# Inverter_540VDC_V2_TEST.net
KiCad netlist of a schematic drawn in Altium Designer
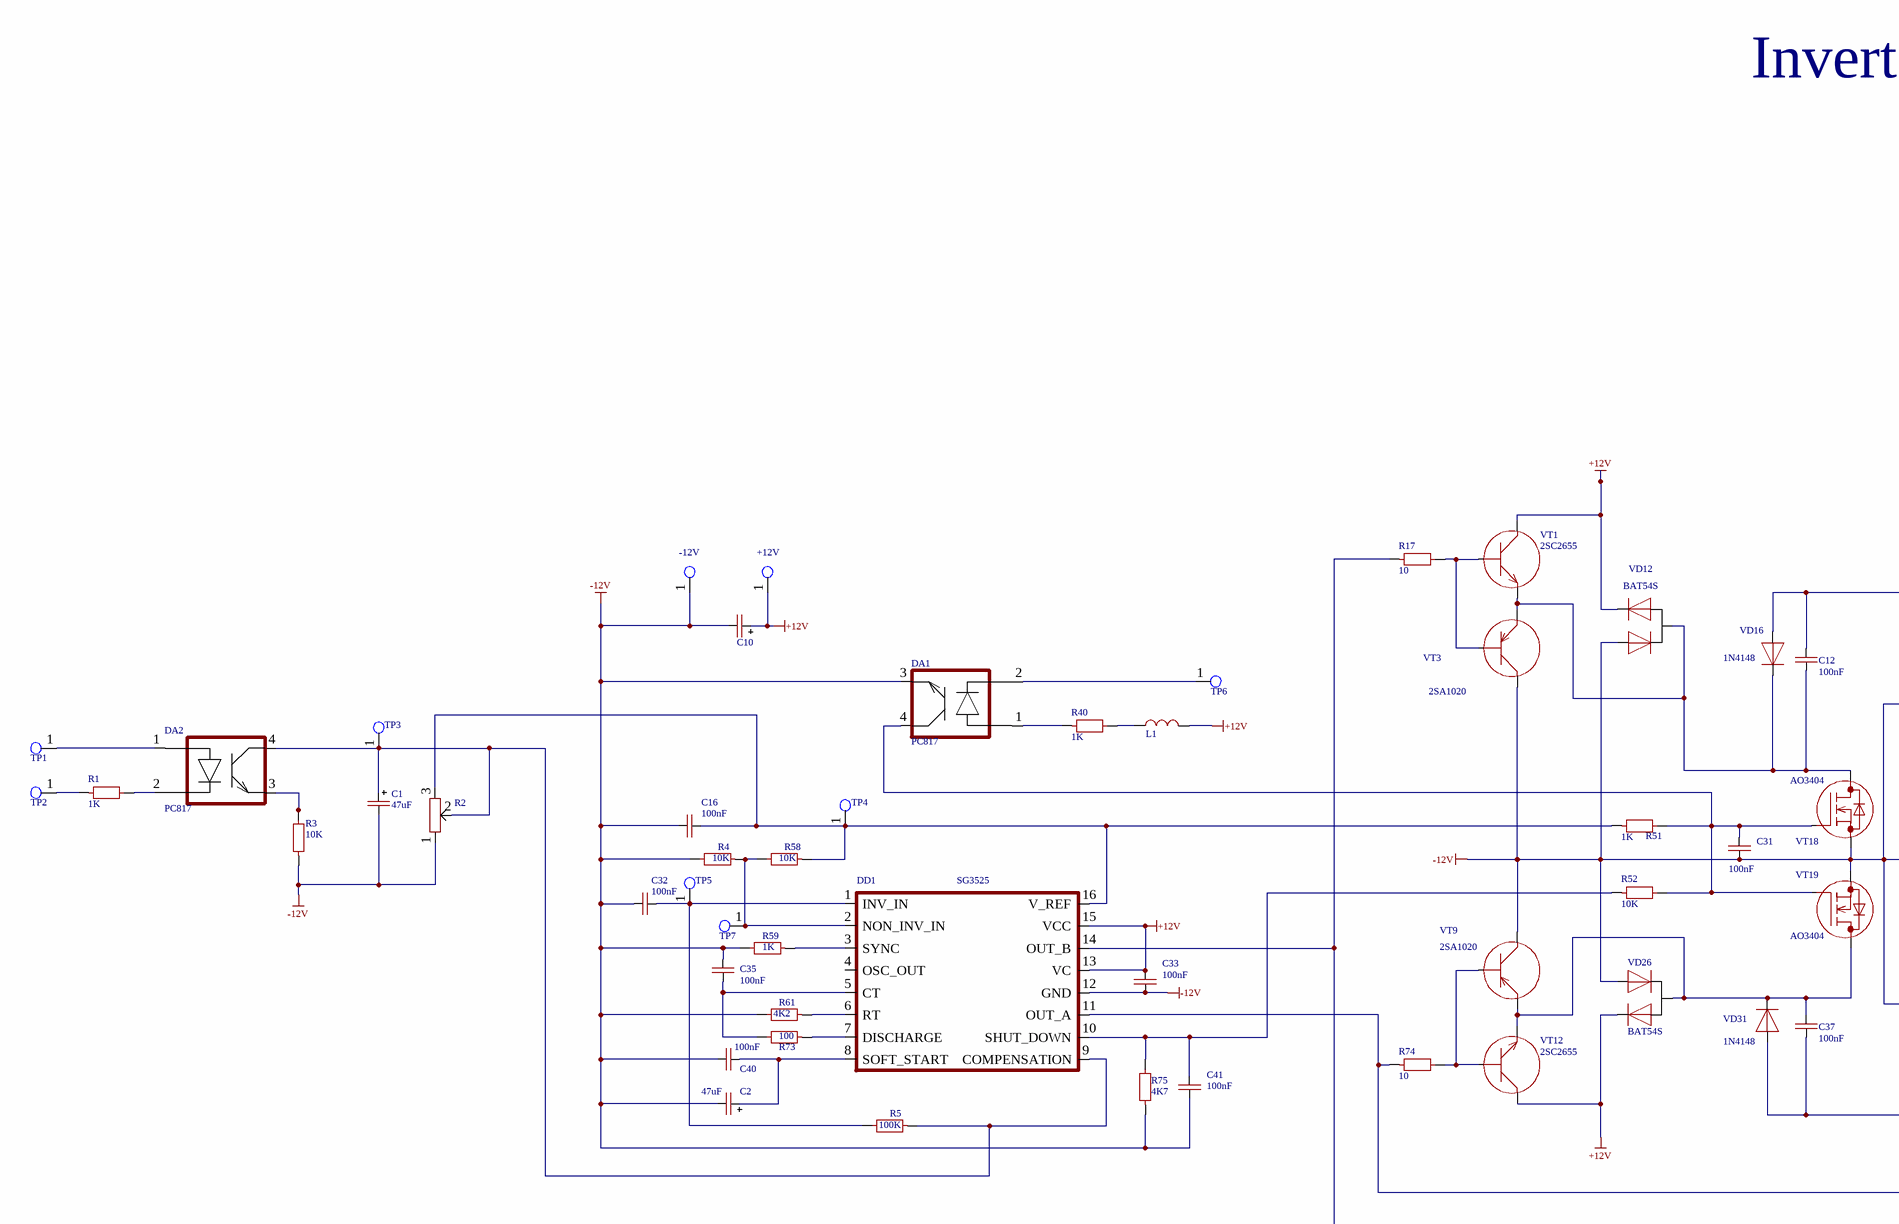
[diagram p0: Inverter_540VDC_V2_TEST.SchDoc, left]
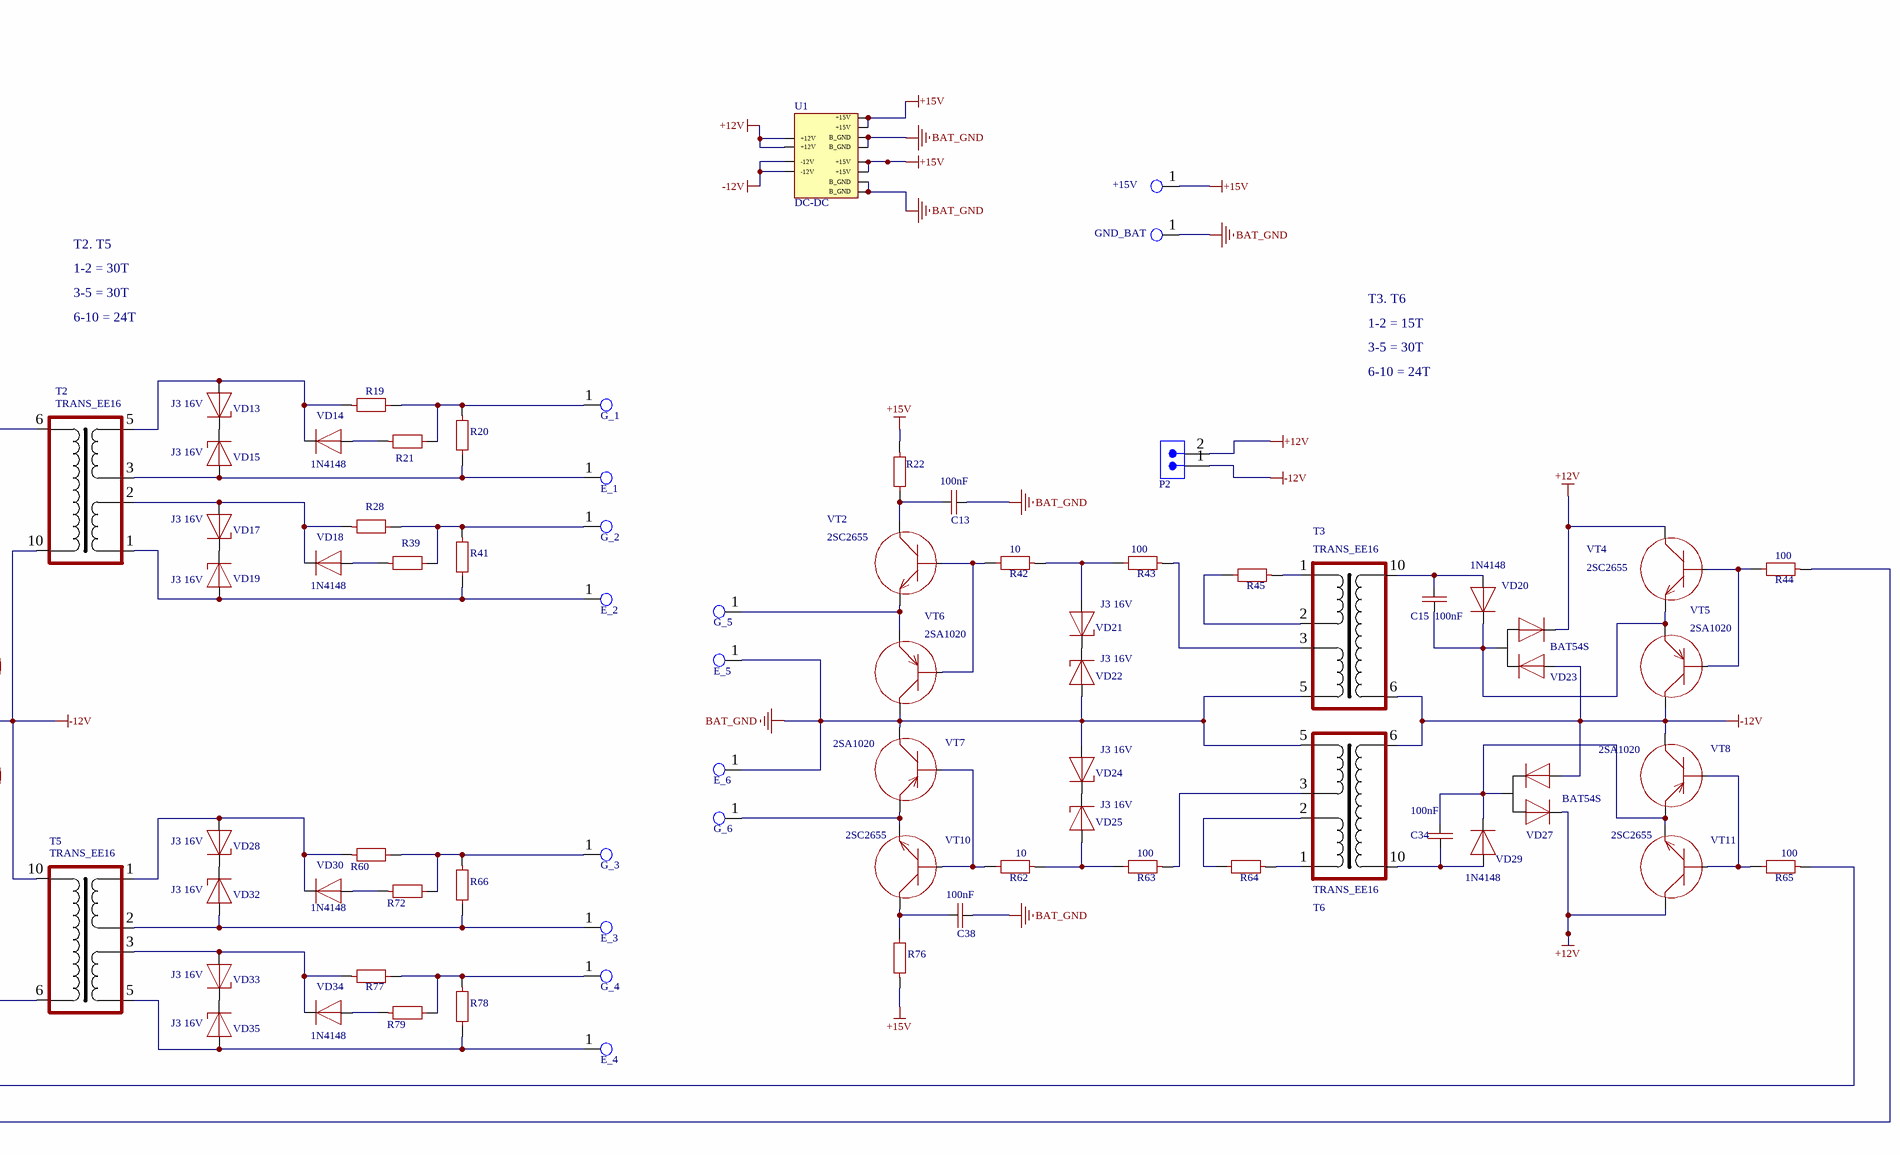
[diagram p1: Inverter_540VDC_V2_TEST.SchDoc, right]

(export (version "E")
  (design (tool "Eeschema 10.0.6"))
  (components
    (comp (ref "+12V")
      (value "Test_Point_PCB")
      (footprint "Test_Point")
      (description "Test_Point")
      (libsource (lib "TEST_POINT") (part "TP_PCB?"))
    )
    (comp (ref "+15V")
      (value "Test_Point_PCB")
      (footprint "Test_Point")
      (description "Test_Point")
      (libsource (lib "TEST_POINT") (part "TP_PCB?"))
    )
    (comp (ref "-12V")
      (value "Test_Point_PCB")
      (footprint "Test_Point")
      (description "Test_Point")
      (libsource (lib "TEST_POINT") (part "TP_PCB?"))
    )
    (comp (ref "C1")
      (value "47uF")
      (footprint "CAP-TAN-C")
      (libsource (lib "PAS_COMPONENTS") (part "CAP-POLAR"))
    )
    (comp (ref "C2")
      (value "47uF")
      (footprint "CAP-TAN-C")
      (libsource (lib "PAS_COMPONENTS") (part "CAP-POLAR"))
    )
    (comp (ref "C10")
      (value "CAP-POLAR")
      (footprint "CAPPOL_SMD_SIZE_E")
      (libsource (lib "PAS_COMPONENTS") (part "CAP-POLAR"))
    )
    (comp (ref "C12")
      (value "100nF")
      (footprint "CAP-1206")
      (libsource (lib "PAS_COMPONENTS") (part "CAP-NON-POLAR"))
    )
    (comp (ref "C13")
      (value "100nF")
      (footprint "CAP-0805")
      (libsource (lib "PAS_COMPONENTS") (part "CAP-NON-POLAR"))
    )
    (comp (ref "C15")
      (value "100nF")
      (footprint "CAP-1206")
      (libsource (lib "PAS_COMPONENTS") (part "CAP-NON-POLAR"))
    )
    (comp (ref "C16")
      (value "100nF")
      (footprint "CAP-0805")
      (libsource (lib "PAS_COMPONENTS") (part "CAP-NON-POLAR"))
    )
    (comp (ref "C31")
      (value "100nF")
      (footprint "CAP-1206")
      (libsource (lib "PAS_COMPONENTS") (part "CAP-NON-POLAR"))
    )
    (comp (ref "C32")
      (value "100nF")
      (footprint "CAP-0805")
      (libsource (lib "PAS_COMPONENTS") (part "CAP-NON-POLAR"))
    )
    (comp (ref "C33")
      (value "100nF")
      (footprint "CAP-0805")
      (libsource (lib "PAS_COMPONENTS") (part "CAP-NON-POLAR"))
    )
    (comp (ref "C34")
      (value "100nF")
      (footprint "CAP-1206")
      (libsource (lib "PAS_COMPONENTS") (part "CAP-NON-POLAR"))
    )
    (comp (ref "C35")
      (value "100nF")
      (footprint "CAP-0805")
      (libsource (lib "PAS_COMPONENTS") (part "CAP-NON-POLAR"))
    )
    (comp (ref "C37")
      (value "100nF")
      (footprint "CAP-1206")
      (libsource (lib "PAS_COMPONENTS") (part "CAP-NON-POLAR"))
    )
    (comp (ref "C38")
      (value "100nF")
      (footprint "CAP-0805")
      (libsource (lib "PAS_COMPONENTS") (part "CAP-NON-POLAR"))
    )
    (comp (ref "C40")
      (value "100nF")
      (footprint "CAP-0805")
      (libsource (lib "PAS_COMPONENTS") (part "CAP-NON-POLAR"))
    )
    (comp (ref "C41")
      (value "100nF")
      (footprint "CAP-0805")
      (libsource (lib "PAS_COMPONENTS") (part "CAP-NON-POLAR"))
    )
    (comp (ref "DA1") (value "PC817") (footprint "4-SMD") (libsource (lib "PC817") (part "PC817")))
    (comp (ref "DA2") (value "PC817") (footprint "4-SMD") (libsource (lib "") (part "PC817_1")))
    (comp (ref "DD1") (value "SG3525") (footprint "SO16-150") (libsource (lib "SG3525") (part "SG3525")))
    (comp (ref "E_1")
      (value "Test_Point_PCB")
      (footprint "Test_Point")
      (description "Test_Point")
      (libsource (lib "TEST_POINT") (part "TP_PCB?"))
    )
    (comp (ref "E_2")
      (value "Test_Point_PCB")
      (footprint "Test_Point")
      (description "Test_Point")
      (libsource (lib "TEST_POINT") (part "TP_PCB?"))
    )
    (comp (ref "E_3")
      (value "Test_Point_PCB")
      (footprint "Test_Point")
      (description "Test_Point")
      (libsource (lib "TEST_POINT") (part "TP_PCB?"))
    )
    (comp (ref "E_4")
      (value "Test_Point_PCB")
      (footprint "Test_Point")
      (description "Test_Point")
      (libsource (lib "TEST_POINT") (part "TP_PCB?"))
    )
    (comp (ref "E_5")
      (value "Test_Point_PCB")
      (footprint "Test_Point")
      (description "Test_Point")
      (libsource (lib "TEST_POINT") (part "TP_PCB?"))
    )
    (comp (ref "E_6")
      (value "Test_Point_PCB")
      (footprint "Test_Point")
      (description "Test_Point")
      (libsource (lib "TEST_POINT") (part "TP_PCB?"))
    )
    (comp (ref "GND_BAT")
      (value "Test_Point_PCB")
      (footprint "Test_Point")
      (description "Test_Point")
      (libsource (lib "TEST_POINT") (part "TP_PCB?"))
    )
    (comp (ref "G_1")
      (value "Test_Point_PCB")
      (footprint "Test_Point")
      (description "Test_Point")
      (libsource (lib "TEST_POINT") (part "TP_PCB?"))
    )
    (comp (ref "G_2")
      (value "Test_Point_PCB")
      (footprint "Test_Point")
      (description "Test_Point")
      (libsource (lib "TEST_POINT") (part "TP_PCB?"))
    )
    (comp (ref "G_3")
      (value "Test_Point_PCB")
      (footprint "Test_Point")
      (description "Test_Point")
      (libsource (lib "TEST_POINT") (part "TP_PCB?"))
    )
    (comp (ref "G_4")
      (value "Test_Point_PCB")
      (footprint "Test_Point")
      (description "Test_Point")
      (libsource (lib "TEST_POINT") (part "TP_PCB?"))
    )
    (comp (ref "G_5")
      (value "Test_Point_PCB")
      (footprint "Test_Point")
      (description "Test_Point")
      (libsource (lib "TEST_POINT") (part "TP_PCB?"))
    )
    (comp (ref "G_6")
      (value "Test_Point_PCB")
      (footprint "Test_Point")
      (description "Test_Point")
      (libsource (lib "TEST_POINT") (part "TP_PCB?"))
    )
    (comp (ref "L1")
      (value "IND-CONST")
      (footprint "IND-7850")
      (libsource (lib "PAS_COMPONENTS") (part "IND-CONST"))
    )
    (comp (ref "P2")
      (value "691701530002B")
      (footprint "691701530002B")
      (description "WR-TBL Series 7015B Open Horizontal PCB Header, SMT, pitch 5.08mm, 2p")
      (fields (field (name "MANUFACTURER") "Wurth Elektronik"))
      (libsource (lib "Altium_WR-TBL (rev23f)") (part "691701530002B"))
    )
    (comp (ref "R1")
      (value "1K")
      (footprint "RES-0805")
      (description "10K")
      (libsource (lib "PAS_COMPONENTS") (part "RES-CONST"))
    )
    (comp (ref "R2") (value "3296W") (footprint "3296W") (libsource (lib "3296W") (part "3296W")))
    (comp (ref "R3")
      (value "10K")
      (footprint "RES-0805")
      (libsource (lib "PAS_COMPONENTS") (part "RES-CONST"))
    )
    (comp (ref "R4")
      (value "10K")
      (footprint "RES-0805")
      (libsource (lib "PAS_COMPONENTS") (part "RES-CONST"))
    )
    (comp (ref "R5")
      (value "100K")
      (footprint "RES-0805")
      (description "10K")
      (libsource (lib "PAS_COMPONENTS") (part "RES-CONST"))
    )
    (comp (ref "R17")
      (value "10")
      (footprint "RES-1206")
      (libsource (lib "PAS_COMPONENTS") (part "RES-CONST"))
    )
    (comp (ref "R19")
      (value "RES-CONST")
      (footprint "RES-1206")
      (libsource (lib "PAS_COMPONENTS") (part "RES-CONST"))
    )
    (comp (ref "R20")
      (value "RES-CONST")
      (footprint "RES-1206")
      (libsource (lib "PAS_COMPONENTS") (part "RES-CONST"))
    )
    (comp (ref "R21")
      (value "RES-CONST")
      (footprint "RES-1206")
      (libsource (lib "PAS_COMPONENTS") (part "RES-CONST"))
    )
    (comp (ref "R22")
      (value "RES-CONST")
      (footprint "RES-2512")
      (libsource (lib "PAS_COMPONENTS") (part "RES-CONST"))
    )
    (comp (ref "R28")
      (value "RES-CONST")
      (footprint "RES-1206")
      (libsource (lib "PAS_COMPONENTS") (part "RES-CONST"))
    )
    (comp (ref "R39")
      (value "RES-CONST")
      (footprint "RES-1206")
      (libsource (lib "PAS_COMPONENTS") (part "RES-CONST"))
    )
    (comp (ref "R40")
      (value "1K")
      (footprint "RES-0805")
      (libsource (lib "PAS_COMPONENTS") (part "RES-CONST"))
    )
    (comp (ref "R41")
      (value "RES-CONST")
      (footprint "RES-1206")
      (libsource (lib "PAS_COMPONENTS") (part "RES-CONST"))
    )
    (comp (ref "R42")
      (value "10")
      (footprint "RES-1206")
      (libsource (lib "PAS_COMPONENTS") (part "RES-CONST"))
    )
    (comp (ref "R43")
      (value "100")
      (footprint "RES-1206")
      (libsource (lib "PAS_COMPONENTS") (part "RES-CONST"))
    )
    (comp (ref "R44")
      (value "100")
      (footprint "RES-1206")
      (libsource (lib "PAS_COMPONENTS") (part "RES-CONST"))
    )
    (comp (ref "R45")
      (value "RES-CONST")
      (footprint "RES-2512")
      (libsource (lib "PAS_COMPONENTS") (part "RES-CONST"))
    )
    (comp (ref "R51")
      (value "1K")
      (footprint "RES-1206")
      (libsource (lib "PAS_COMPONENTS") (part "RES-CONST"))
    )
    (comp (ref "R52")
      (value "10K")
      (footprint "RES-1206")
      (libsource (lib "PAS_COMPONENTS") (part "RES-CONST"))
    )
    (comp (ref "R58")
      (value "10K")
      (footprint "RES-0805")
      (libsource (lib "PAS_COMPONENTS") (part "RES-CONST"))
    )
    (comp (ref "R59")
      (value "1K")
      (footprint "RES-0805")
      (libsource (lib "PAS_COMPONENTS") (part "RES-CONST"))
    )
    (comp (ref "R60")
      (value "RES-CONST")
      (footprint "RES-1206")
      (libsource (lib "PAS_COMPONENTS") (part "RES-CONST"))
    )
    (comp (ref "R61")
      (value "4K2")
      (footprint "RES-0805")
      (libsource (lib "PAS_COMPONENTS") (part "RES-CONST"))
    )
    (comp (ref "R62")
      (value "10")
      (footprint "RES-1206")
      (libsource (lib "PAS_COMPONENTS") (part "RES-CONST"))
    )
    (comp (ref "R63")
      (value "100")
      (footprint "RES-1206")
      (libsource (lib "PAS_COMPONENTS") (part "RES-CONST"))
    )
    (comp (ref "R64")
      (value "RES-CONST")
      (footprint "RES-2512")
      (libsource (lib "PAS_COMPONENTS") (part "RES-CONST"))
    )
    (comp (ref "R65")
      (value "100")
      (footprint "RES-1206")
      (libsource (lib "PAS_COMPONENTS") (part "RES-CONST"))
    )
    (comp (ref "R66")
      (value "RES-CONST")
      (footprint "RES-1206")
      (libsource (lib "PAS_COMPONENTS") (part "RES-CONST"))
    )
    (comp (ref "R72")
      (value "RES-CONST")
      (footprint "RES-1206")
      (libsource (lib "PAS_COMPONENTS") (part "RES-CONST"))
    )
    (comp (ref "R73")
      (value "100")
      (footprint "RES-0805")
      (libsource (lib "PAS_COMPONENTS") (part "RES-CONST"))
    )
    (comp (ref "R74")
      (value "10")
      (footprint "RES-1206")
      (libsource (lib "PAS_COMPONENTS") (part "RES-CONST"))
    )
    (comp (ref "R75")
      (value "4K7")
      (footprint "RES-0805")
      (libsource (lib "PAS_COMPONENTS") (part "RES-CONST"))
    )
    (comp (ref "R76")
      (value "RES-CONST")
      (footprint "RES-2512")
      (libsource (lib "PAS_COMPONENTS") (part "RES-CONST"))
    )
    (comp (ref "R77")
      (value "RES-CONST")
      (footprint "RES-1206")
      (libsource (lib "PAS_COMPONENTS") (part "RES-CONST"))
    )
    (comp (ref "R78")
      (value "RES-CONST")
      (footprint "RES-1206")
      (libsource (lib "PAS_COMPONENTS") (part "RES-CONST"))
    )
    (comp (ref "R79")
      (value "RES-CONST")
      (footprint "RES-1206")
      (libsource (lib "PAS_COMPONENTS") (part "RES-CONST"))
    )
    (comp (ref "T2")
      (value "TRANS_EE16")
      (footprint "TRANS_EE16")
      (libsource (lib "TRANS_EE16") (part "TRANS_EE16"))
    )
    (comp (ref "T3")
      (value "TRANS_EE16")
      (footprint "TRANS_EE16")
      (libsource (lib "TRANS_EE16") (part "TRANS_EE16"))
    )
    (comp (ref "T5") (value "TRANS_EE16") (footprint "TRANS_EE16") (libsource (lib "") (part "TRANS_EE16_1")))
    (comp (ref "T6") (value "TRANS_EE16") (footprint "TRANS_EE16") (libsource (lib "") (part "TRANS_EE16_1")))
    (comp (ref "TP1")
      (value "Test_Point_PCB")
      (footprint "Test_Point")
      (description "Test_Point")
      (libsource (lib "TEST_POINT") (part "TP_PCB?"))
    )
    (comp (ref "TP2")
      (value "Test_Point_PCB")
      (footprint "Test_Point")
      (description "Test_Point")
      (libsource (lib "TEST_POINT") (part "TP_PCB?"))
    )
    (comp (ref "TP3")
      (value "Test_Point_PCB")
      (footprint "Test_Point")
      (description "Test_Point")
      (libsource (lib "TEST_POINT") (part "TP_PCB?"))
    )
    (comp (ref "TP4")
      (value "Test_Point_PCB")
      (footprint "Test_Point")
      (description "Test_Point")
      (libsource (lib "TEST_POINT") (part "TP_PCB?"))
    )
    (comp (ref "TP5")
      (value "Test_Point_PCB")
      (footprint "Test_Point")
      (description "Test_Point")
      (libsource (lib "TEST_POINT") (part "TP_PCB?"))
    )
    (comp (ref "TP6")
      (value "Test_Point_PCB")
      (footprint "Test_Point")
      (description "Test_Point")
      (libsource (lib "TEST_POINT") (part "TP_PCB?"))
    )
    (comp (ref "TP7")
      (value "Test_Point_PCB")
      (footprint "Test_Point")
      (description "Test_Point")
      (libsource (lib "TEST_POINT") (part "TP_PCB?"))
    )
    (comp (ref "U1")
      (value "DC-DC")
      (footprint "DC-DC_Bridge")
      (libsource (lib "PWM_Controllers") (part "DC-DC/12-18VDC"))
    )
    (comp (ref "VD12") (value "BAT54S") (footprint "SOT23-3") (libsource (lib "DIODES") (part "DIODE-4")))
    (comp (ref "VD13") (value "J3 16V") (footprint "SOD-123") (libsource (lib "DIODES") (part "ZENER")))
    (comp (ref "VD14") (value "1N4148") (footprint "SOD-123") (libsource (lib "DIODES") (part "DIODE")))
    (comp (ref "VD15") (value "J3 16V") (footprint "SOD-123") (libsource (lib "DIODES") (part "ZENER")))
    (comp (ref "VD16") (value "1N4148") (footprint "SOD-123") (libsource (lib "DIODES") (part "DIODE")))
    (comp (ref "VD17") (value "J3 16V") (footprint "SOD-123") (libsource (lib "DIODES") (part "ZENER")))
    (comp (ref "VD18") (value "1N4148") (footprint "SOD-123") (libsource (lib "DIODES") (part "DIODE")))
    (comp (ref "VD19") (value "J3 16V") (footprint "SOD-123") (libsource (lib "DIODES") (part "ZENER")))
    (comp (ref "VD20") (value "1N4148") (footprint "SOD-123") (libsource (lib "DIODES") (part "DIODE")))
    (comp (ref "VD21") (value "J3 16V") (footprint "SOD-123") (libsource (lib "DIODES") (part "ZENER")))
    (comp (ref "VD22") (value "J3 16V") (footprint "SOD-123") (libsource (lib "DIODES") (part "ZENER")))
    (comp (ref "VD23") (value "BAT54S") (footprint "SOT23-3") (libsource (lib "DIODES") (part "DIODE-4")))
    (comp (ref "VD24") (value "J3 16V") (footprint "SOD-123") (libsource (lib "DIODES") (part "ZENER")))
    (comp (ref "VD25") (value "J3 16V") (footprint "SOD-123") (libsource (lib "DIODES") (part "ZENER")))
    (comp (ref "VD26") (value "BAT54S") (footprint "SOT23-3") (libsource (lib "DIODES") (part "DIODE-4")))
    (comp (ref "VD27") (value "BAT54S") (footprint "SOT23-3") (libsource (lib "DIODES") (part "DIODE-4")))
    (comp (ref "VD28") (value "J3 16V") (footprint "SOD-123") (libsource (lib "DIODES") (part "ZENER")))
    (comp (ref "VD29") (value "1N4148") (footprint "SOD-123") (libsource (lib "DIODES") (part "DIODE")))
    (comp (ref "VD30") (value "1N4148") (footprint "SOD-123") (libsource (lib "DIODES") (part "DIODE")))
    (comp (ref "VD31") (value "1N4148") (footprint "SOD-123") (libsource (lib "DIODES") (part "DIODE")))
    (comp (ref "VD32") (value "J3 16V") (footprint "SOD-123") (libsource (lib "DIODES") (part "ZENER")))
    (comp (ref "VD33") (value "J3 16V") (footprint "SOD-123") (libsource (lib "DIODES") (part "ZENER")))
    (comp (ref "VD34") (value "1N4148") (footprint "SOD-123") (libsource (lib "DIODES") (part "DIODE")))
    (comp (ref "VD35") (value "J3 16V") (footprint "SOD-123") (libsource (lib "DIODES") (part "ZENER")))
    (comp (ref "VT1")
      (value "2SC2655")
      (footprint "SOT-89")
      (libsource (lib "TRANSISTORS") (part "BIPOLAR-NPN-BEC"))
    )
    (comp (ref "VT2")
      (value "2SC2655")
      (footprint "SOT-89")
      (libsource (lib "TRANSISTORS") (part "BIPOLAR-NPN-BEC"))
    )
    (comp (ref "VT3")
      (value "2SA1020")
      (footprint "SOT-89")
      (libsource (lib "TRANSISTORS") (part "BIPOLAR-PNP-BCE"))
    )
    (comp (ref "VT4")
      (value "2SC2655")
      (footprint "SOT-89")
      (libsource (lib "TRANSISTORS") (part "BIPOLAR-NPN-BEC"))
    )
    (comp (ref "VT5")
      (value "2SA1020")
      (footprint "SOT-89")
      (libsource (lib "TRANSISTORS") (part "BIPOLAR-PNP-BCE"))
    )
    (comp (ref "VT6")
      (value "2SA1020")
      (footprint "SOT-89")
      (libsource (lib "TRANSISTORS") (part "BIPOLAR-PNP-BCE"))
    )
    (comp (ref "VT7")
      (value "2SA1020")
      (footprint "SOT-89")
      (libsource (lib "TRANSISTORS") (part "BIPOLAR-PNP-BCE"))
    )
    (comp (ref "VT8")
      (value "2SA1020")
      (footprint "SOT-89")
      (libsource (lib "TRANSISTORS") (part "BIPOLAR-PNP-BCE"))
    )
    (comp (ref "VT9")
      (value "2SA1020")
      (footprint "SOT-89")
      (libsource (lib "TRANSISTORS") (part "BIPOLAR-PNP-BCE"))
    )
    (comp (ref "VT10")
      (value "2SC2655")
      (footprint "SOT-89")
      (libsource (lib "TRANSISTORS") (part "BIPOLAR-NPN-BEC"))
    )
    (comp (ref "VT11")
      (value "2SC2655")
      (footprint "SOT-89")
      (libsource (lib "TRANSISTORS") (part "BIPOLAR-NPN-BEC"))
    )
    (comp (ref "VT12")
      (value "2SC2655")
      (footprint "SOT-89")
      (libsource (lib "TRANSISTORS") (part "BIPOLAR-NPN-BEC"))
    )
    (comp (ref "VT18")
      (value "AO3404")
      (footprint "SOT23-3")
      (libsource (lib "TRANSISTORS") (part "MOSFET-N-GDS"))
    )
    (comp (ref "VT19")
      (value "AO3404")
      (footprint "SOT23-3")
      (libsource (lib "TRANSISTORS") (part "MOSFET-N-GDS"))
    )
  )
  (nets
    (net (code "1") (name "+12V") (class "Default")
      (node (ref "+12V") (pin "1") (pinfunction "G9_1") (pintype "passive"))
      (node (ref "C10") (pin "1") (pinfunction "+_1") (pintype "passive"))
      (node (ref "C33") (pin "2") (pinfunction "2_2") (pintype "passive"))
      (node (ref "DD1") (pin "13") (pinfunction "VC_13") (pintype "passive"))
      (node (ref "DD1") (pin "15") (pinfunction "VCC_15") (pintype "passive"))
      (node (ref "L1") (pin "2") (pinfunction "2_2") (pintype "passive"))
      (node (ref "P2") (pin "2") (pinfunction "2_2") (pintype "passive"))
      (node (ref "U1") (pin "8") (pinfunction "+12V_8") (pintype "passive"))
      (node (ref "U1") (pin "9") (pinfunction "+12V_9") (pintype "passive"))
      (node (ref "VD12") (pin "2") (pinfunction "C_2") (pintype "passive"))
      (node (ref "VD23") (pin "2") (pinfunction "C_2") (pintype "passive"))
      (node (ref "VD26") (pin "2") (pinfunction "C_2") (pintype "passive"))
      (node (ref "VD27") (pin "2") (pinfunction "C_2") (pintype "passive"))
      (node (ref "VT1") (pin "2") (pinfunction "C_2") (pintype "passive"))
      (node (ref "VT11") (pin "2") (pinfunction "C_2") (pintype "passive"))
      (node (ref "VT12") (pin "2") (pinfunction "C_2") (pintype "passive"))
      (node (ref "VT4") (pin "2") (pinfunction "C_2") (pintype "passive"))
    )
    (net (code "2") (name "+15V") (class "Default")
      (node (ref "+15V") (pin "1") (pinfunction "G9_1") (pintype "passive"))
      (node (ref "R22") (pin "1") (pinfunction "1_1") (pintype "passive"))
      (node (ref "R76") (pin "1") (pinfunction "1_1") (pintype "passive"))
      (node (ref "U1") (pin "1") (pinfunction "+15V_1") (pintype "passive"))
      (node (ref "U1") (pin "17") (pinfunction "+15V_17") (pintype "passive"))
      (node (ref "U1") (pin "18") (pinfunction "+15V_18") (pintype "passive"))
      (node (ref "U1") (pin "2") (pinfunction "+15V_2") (pintype "passive"))
    )
    (net (code "3") (name "-12V") (class "Default")
      (node (ref "-12V") (pin "1") (pinfunction "G9_1") (pintype "passive"))
      (node (ref "C1") (pin "2") (pinfunction "-_2") (pintype "passive"))
      (node (ref "C10") (pin "2") (pinfunction "-_2") (pintype "passive"))
      (node (ref "C16") (pin "2") (pinfunction "2_2") (pintype "passive"))
      (node (ref "C2") (pin "2") (pinfunction "-_2") (pintype "passive"))
      (node (ref "C31") (pin "1") (pinfunction "1_1") (pintype "passive"))
      (node (ref "C32") (pin "2") (pinfunction "2_2") (pintype "passive"))
      (node (ref "C33") (pin "1") (pinfunction "1_1") (pintype "passive"))
      (node (ref "C35") (pin "1") (pinfunction "1_1") (pintype "passive"))
      (node (ref "C40") (pin "2") (pinfunction "2_2") (pintype "passive"))
      (node (ref "C41") (pin "1") (pinfunction "1_1") (pintype "passive"))
      (node (ref "DA1") (pin "3") (pinfunction "EMITTER_3") (pintype "passive"))
      (node (ref "DD1") (pin "12") (pinfunction "GND_12") (pintype "passive"))
      (node (ref "P2") (pin "1") (pinfunction "1_1") (pintype "passive"))
      (node (ref "R2") (pin "1") (pinfunction "1_1") (pintype "passive"))
      (node (ref "R3") (pin "1") (pinfunction "1_1") (pintype "passive"))
      (node (ref "R4") (pin "2") (pinfunction "2_2") (pintype "passive"))
      (node (ref "R59") (pin "2") (pinfunction "2_2") (pintype "passive"))
      (node (ref "R61") (pin "2") (pinfunction "2_2") (pintype "passive"))
      (node (ref "R75") (pin "1") (pinfunction "1_1") (pintype "passive"))
      (node (ref "T2") (pin "10") (pintype "passive"))
      (node (ref "T3") (pin "6") (pintype "passive"))
      (node (ref "T5") (pin "10") (pintype "passive"))
      (node (ref "T6") (pin "6") (pintype "passive"))
      (node (ref "U1") (pin "10") (pinfunction "-12V_10") (pintype "passive"))
      (node (ref "U1") (pin "11") (pinfunction "-12V_11") (pintype "passive"))
      (node (ref "VD12") (pin "1") (pinfunction "A_1") (pintype "passive"))
      (node (ref "VD23") (pin "1") (pinfunction "A_1") (pintype "passive"))
      (node (ref "VD26") (pin "1") (pinfunction "A_1") (pintype "passive"))
      (node (ref "VD27") (pin "1") (pinfunction "A_1") (pintype "passive"))
      (node (ref "VT18") (pin "2") (pinfunction "S_2") (pintype "passive"))
      (node (ref "VT19") (pin "2") (pinfunction "S_2") (pintype "passive"))
      (node (ref "VT3") (pin "2") (pinfunction "C_2") (pintype "passive"))
      (node (ref "VT5") (pin "2") (pinfunction "C_2") (pintype "passive"))
      (node (ref "VT8") (pin "2") (pinfunction "C_2") (pintype "passive"))
      (node (ref "VT9") (pin "2") (pinfunction "C_2") (pintype "passive"))
    )
    (net (code "4") (name "BAT_GND") (class "Default")
      (node (ref "C13") (pin "1") (pinfunction "1_1") (pintype "passive"))
      (node (ref "C38") (pin "1") (pinfunction "1_1") (pintype "passive"))
      (node (ref "E_5") (pin "1") (pinfunction "G9_1") (pintype "passive"))
      (node (ref "E_6") (pin "1") (pinfunction "G9_1") (pintype "passive"))
      (node (ref "GND_BAT") (pin "1") (pinfunction "G9_1") (pintype "passive"))
      (node (ref "T3") (pin "5") (pintype "passive"))
      (node (ref "T6") (pin "5") (pintype "passive"))
      (node (ref "U1") (pin "15") (pinfunction "B_GND_15") (pintype "passive"))
      (node (ref "U1") (pin "16") (pinfunction "B_GND_16") (pintype "passive"))
      (node (ref "U1") (pin "3") (pinfunction "B_GND_3") (pintype "passive"))
      (node (ref "U1") (pin "4") (pinfunction "B_GND_4") (pintype "passive"))
      (node (ref "VD22") (pin "2") (pinfunction "A_2") (pintype "passive"))
      (node (ref "VD24") (pin "2") (pinfunction "A_2") (pintype "passive"))
      (node (ref "VT6") (pin "2") (pinfunction "C_2") (pintype "passive"))
      (node (ref "VT7") (pin "2") (pinfunction "C_2") (pintype "passive"))
    )
    (net (code "5") (name "Net-(C1-+)") (class "Default")
      (node (ref "C1") (pin "1") (pinfunction "+_1") (pintype "passive"))
      (node (ref "DA2") (pin "4") (pinfunction "COLLECTOR_4") (pintype "passive"))
      (node (ref "DD1") (pin "9") (pinfunction "COMPENSATION_9") (pintype "passive"))
      (node (ref "R2") (pin "2") (pinfunction "2_2") (pintype "passive"))
      (node (ref "R5") (pin "1") (pinfunction "1_1") (pintype "passive"))
      (node (ref "TP3") (pin "1") (pinfunction "G9_1") (pintype "passive"))
    )
    (net (code "6") (name "Net-(C2-+)") (class "Default")
      (node (ref "C2") (pin "1") (pinfunction "+_1") (pintype "passive"))
      (node (ref "C40") (pin "1") (pinfunction "1_1") (pintype "passive"))
      (node (ref "DD1") (pin "8") (pinfunction "SOFT_START_8") (pintype "passive"))
    )
    (net (code "7") (name "Net-(DA1-ANODE)") (class "Default")
      (node (ref "DA1") (pin "1") (pinfunction "ANODE_1") (pintype "passive"))
      (node (ref "R40") (pin "1") (pinfunction "1_1") (pintype "passive"))
    )
    (net (code "8") (name "Net-(DA1-CATHODE)") (class "Default")
      (node (ref "DA1") (pin "2") (pinfunction "CATHODE_2") (pintype "passive"))
      (node (ref "TP6") (pin "1") (pinfunction "G9_1") (pintype "passive"))
    )
    (net (code "9") (name "Net-(DA1-COLLECTOR)") (class "Default")
      (node (ref "C31") (pin "2") (pinfunction "2_2") (pintype "passive"))
      (node (ref "DA1") (pin "4") (pinfunction "COLLECTOR_4") (pintype "passive"))
      (node (ref "R51") (pin "2") (pinfunction "2_2") (pintype "passive"))
      (node (ref "R52") (pin "2") (pinfunction "2_2") (pintype "passive"))
      (node (ref "VT18") (pin "1") (pinfunction "G_1") (pintype "passive"))
      (node (ref "VT19") (pin "1") (pinfunction "G_1") (pintype "passive"))
    )
    (net (code "10") (name "Net-(DA2-ANODE)") (class "Default")
      (node (ref "DA2") (pin "1") (pinfunction "ANODE_1") (pintype "passive"))
      (node (ref "TP1") (pin "1") (pinfunction "G9_1") (pintype "passive"))
    )
    (net (code "11") (name "Net-(DA2-CATHODE)") (class "Default")
      (node (ref "DA2") (pin "2") (pinfunction "CATHODE_2") (pintype "passive"))
      (node (ref "R1") (pin "2") (pinfunction "2_2") (pintype "passive"))
    )
    (net (code "12") (name "Net-(DA2-EMITTER)") (class "Default")
      (node (ref "DA2") (pin "3") (pinfunction "EMITTER_3") (pintype "passive"))
      (node (ref "R3") (pin "2") (pinfunction "2_2") (pintype "passive"))
    )
    (net (code "13") (name "Net-(DD1-CT)") (class "Default")
      (node (ref "C35") (pin "2") (pinfunction "2_2") (pintype "passive"))
      (node (ref "DD1") (pin "5") (pinfunction "CT_5") (pintype "passive"))
      (node (ref "R73") (pin "2") (pinfunction "2_2") (pintype "passive"))
    )
    (net (code "14") (name "Net-(DD1-DISCHARGE)") (class "Default")
      (node (ref "DD1") (pin "7") (pinfunction "DISCHARGE_7") (pintype "passive"))
      (node (ref "R73") (pin "1") (pinfunction "1_1") (pintype "passive"))
    )
    (net (code "15") (name "Net-(DD1-INV_IN)") (class "Default")
      (node (ref "C32") (pin "1") (pinfunction "1_1") (pintype "passive"))
      (node (ref "DD1") (pin "1") (pinfunction "INV_IN_1") (pintype "passive"))
      (node (ref "R5") (pin "2") (pinfunction "2_2") (pintype "passive"))
      (node (ref "TP5") (pin "1") (pinfunction "G9_1") (pintype "passive"))
    )
    (net (code "16") (name "Net-(DD1-NON_INV_IN)") (class "Default")
      (node (ref "DD1") (pin "2") (pinfunction "NON_INV_IN_2") (pintype "passive"))
      (node (ref "R4") (pin "1") (pinfunction "1_1") (pintype "passive"))
      (node (ref "R58") (pin "2") (pinfunction "2_2") (pintype "passive"))
      (node (ref "TP7") (pin "1") (pinfunction "G9_1") (pintype "passive"))
    )
    (net (code "17") (name "Net-(DD1-OUT_A)") (class "Default")
      (node (ref "DD1") (pin "11") (pinfunction "OUT_A_11") (pintype "passive"))
      (node (ref "R65") (pin "1") (pinfunction "1_1") (pintype "passive"))
      (node (ref "R74") (pin "1") (pinfunction "1_1") (pintype "passive"))
    )
    (net (code "18") (name "Net-(DD1-OUT_B)") (class "Default")
      (node (ref "DD1") (pin "14") (pinfunction "OUT_B_14") (pintype "passive"))
      (node (ref "R17") (pin "1") (pinfunction "1_1") (pintype "passive"))
      (node (ref "R44") (pin "1") (pinfunction "1_1") (pintype "passive"))
    )
    (net (code "19") (name "Net-(DD1-RT)") (class "Default")
      (node (ref "DD1") (pin "6") (pinfunction "RT_6") (pintype "passive"))
      (node (ref "R61") (pin "1") (pinfunction "1_1") (pintype "passive"))
    )
    (net (code "20") (name "Net-(DD1-SHUT_DOWN)") (class "Default")
      (node (ref "C41") (pin "2") (pinfunction "2_2") (pintype "passive"))
      (node (ref "DD1") (pin "10") (pinfunction "SHUT_DOWN_10") (pintype "passive"))
      (node (ref "R52") (pin "1") (pinfunction "1_1") (pintype "passive"))
      (node (ref "R75") (pin "2") (pinfunction "2_2") (pintype "passive"))
    )
    (net (code "21") (name "Net-(DD1-SYNC)") (class "Default")
      (node (ref "DD1") (pin "3") (pinfunction "SYNC_3") (pintype "passive"))
      (node (ref "R59") (pin "1") (pinfunction "1_1") (pintype "passive"))
    )
    (net (code "22") (name "Net-(DD1-V_REF)") (class "Default")
      (node (ref "C16") (pin "1") (pinfunction "1_1") (pintype "passive"))
      (node (ref "DD1") (pin "16") (pinfunction "V_REF_16") (pintype "passive"))
      (node (ref "R2") (pin "3") (pinfunction "3_3") (pintype "passive"))
      (node (ref "R51") (pin "1") (pinfunction "1_1") (pintype "passive"))
      (node (ref "R58") (pin "1") (pinfunction "1_1") (pintype "passive"))
      (node (ref "TP4") (pin "1") (pinfunction "G9_1") (pintype "passive"))
    )
    (net (code "23") (name "Net-(E_1-G9)") (class "Default")
      (node (ref "E_1") (pin "1") (pinfunction "G9_1") (pintype "passive"))
      (node (ref "R20") (pin "2") (pinfunction "2_2") (pintype "passive"))
      (node (ref "T2") (pin "3") (pintype "passive"))
      (node (ref "VD15") (pin "2") (pinfunction "A_2") (pintype "passive"))
    )
    (net (code "24") (name "Net-(E_2-G9)") (class "Default")
      (node (ref "E_2") (pin "1") (pinfunction "G9_1") (pintype "passive"))
      (node (ref "R41") (pin "2") (pinfunction "2_2") (pintype "passive"))
      (node (ref "T2") (pin "1") (pintype "passive"))
      (node (ref "VD19") (pin "2") (pinfunction "A_2") (pintype "passive"))
    )
    (net (code "25") (name "Net-(E_3-G9)") (class "Default")
      (node (ref "E_3") (pin "1") (pinfunction "G9_1") (pintype "passive"))
      (node (ref "R66") (pin "2") (pinfunction "2_2") (pintype "passive"))
      (node (ref "T5") (pin "2") (pintype "passive"))
      (node (ref "VD32") (pin "2") (pinfunction "A_2") (pintype "passive"))
    )
    (net (code "26") (name "Net-(E_4-G9)") (class "Default")
      (node (ref "E_4") (pin "1") (pinfunction "G9_1") (pintype "passive"))
      (node (ref "R78") (pin "2") (pinfunction "2_2") (pintype "passive"))
      (node (ref "T5") (pin "5") (pintype "passive"))
      (node (ref "VD35") (pin "2") (pinfunction "A_2") (pintype "passive"))
    )
    (net (code "27") (name "Net-(G_1-G9)") (class "Default")
      (node (ref "G_1") (pin "1") (pinfunction "G9_1") (pintype "passive"))
      (node (ref "R19") (pin "2") (pinfunction "2_2") (pintype "passive"))
      (node (ref "R20") (pin "1") (pinfunction "1_1") (pintype "passive"))
      (node (ref "R21") (pin "2") (pinfunction "2_2") (pintype "passive"))
    )
    (net (code "28") (name "Net-(G_2-G9)") (class "Default")
      (node (ref "G_2") (pin "1") (pinfunction "G9_1") (pintype "passive"))
      (node (ref "R28") (pin "2") (pinfunction "2_2") (pintype "passive"))
      (node (ref "R39") (pin "2") (pinfunction "2_2") (pintype "passive"))
      (node (ref "R41") (pin "1") (pinfunction "1_1") (pintype "passive"))
    )
    (net (code "29") (name "Net-(G_3-G9)") (class "Default")
      (node (ref "G_3") (pin "1") (pinfunction "G9_1") (pintype "passive"))
      (node (ref "R60") (pin "2") (pinfunction "2_2") (pintype "passive"))
      (node (ref "R66") (pin "1") (pinfunction "1_1") (pintype "passive"))
      (node (ref "R72") (pin "2") (pinfunction "2_2") (pintype "passive"))
    )
    (net (code "30") (name "Net-(G_4-G9)") (class "Default")
      (node (ref "G_4") (pin "1") (pinfunction "G9_1") (pintype "passive"))
      (node (ref "R77") (pin "2") (pinfunction "2_2") (pintype "passive"))
      (node (ref "R78") (pin "1") (pinfunction "1_1") (pintype "passive"))
      (node (ref "R79") (pin "2") (pinfunction "2_2") (pintype "passive"))
    )
    (net (code "31") (name "Net-(G_5-G9)") (class "Default")
      (node (ref "G_5") (pin "1") (pinfunction "G9_1") (pintype "passive"))
      (node (ref "VT2") (pin "3") (pinfunction "E_3") (pintype "passive"))
      (node (ref "VT6") (pin "3") (pinfunction "E_3") (pintype "passive"))
    )
    (net (code "32") (name "Net-(G_6-G9)") (class "Default")
      (node (ref "G_6") (pin "1") (pinfunction "G9_1") (pintype "passive"))
      (node (ref "VT10") (pin "3") (pinfunction "E_3") (pintype "passive"))
      (node (ref "VT7") (pin "3") (pinfunction "E_3") (pintype "passive"))
    )
    (net (code "33") (name "Net-(L1-Pad1)") (class "Default")
      (node (ref "L1") (pin "1") (pinfunction "1_1") (pintype "passive"))
      (node (ref "R40") (pin "2") (pinfunction "2_2") (pintype "passive"))
    )
    (net (code "34") (name "Net-(R43-Pad1)") (class "Default")
      (node (ref "R43") (pin "1") (pinfunction "1_1") (pintype "passive"))
      (node (ref "T3") (pin "3") (pintype "passive"))
    )
    (net (code "35") (name "Net-(R45-Pad1)") (class "Default")
      (node (ref "R45") (pin "1") (pinfunction "1_1") (pintype "passive"))
      (node (ref "T3") (pin "1") (pintype "passive"))
    )
    (net (code "36") (name "Net-(R45-Pad2)") (class "Default")
      (node (ref "R45") (pin "2") (pinfunction "2_2") (pintype "passive"))
      (node (ref "T3") (pin "2") (pintype "passive"))
    )
    (net (code "37") (name "Net-(R63-Pad1)") (class "Default")
      (node (ref "R63") (pin "1") (pinfunction "1_1") (pintype "passive"))
      (node (ref "T6") (pin "3") (pintype "passive"))
    )
    (net (code "38") (name "Net-(R64-Pad1)") (class "Default")
      (node (ref "R64") (pin "1") (pinfunction "1_1") (pintype "passive"))
      (node (ref "T6") (pin "1") (pintype "passive"))
    )
    (net (code "39") (name "Net-(R64-Pad2)") (class "Default")
      (node (ref "R64") (pin "2") (pinfunction "2_2") (pintype "passive"))
      (node (ref "T6") (pin "2") (pintype "passive"))
    )
    (net (code "40") (name "Net-(TP2-G9)") (class "Default")
      (node (ref "R1") (pin "1") (pinfunction "1_1") (pintype "passive"))
      (node (ref "TP2") (pin "1") (pinfunction "G9_1") (pintype "passive"))
    )
    (net (code "41") (name "Net-(VD12-x)") (class "Default")
      (node (ref "C12") (pin "1") (pinfunction "1_1") (pintype "passive"))
      (node (ref "VD12") (pin "3") (pinfunction "x_3") (pintype "passive"))
      (node (ref "VD16") (pin "1") (pinfunction "C_1") (pintype "passive"))
      (node (ref "VT1") (pin "3") (pinfunction "E_3") (pintype "passive"))
      (node (ref "VT18") (pin "3") (pinfunction "D_3") (pintype "passive"))
      (node (ref "VT3") (pin "3") (pinfunction "E_3") (pintype "passive"))
    )
    (net (code "42") (name "Net-(VD13-A)") (class "Default")
      (node (ref "R19") (pin "1") (pinfunction "1_1") (pintype "passive"))
      (node (ref "T2") (pin "5") (pintype "passive"))
      (node (ref "VD13") (pin "2") (pinfunction "A_2") (pintype "passive"))
      (node (ref "VD14") (pin "1") (pinfunction "C_1") (pintype "passive"))
    )
    (net (code "43") (name "Net-(VD13-C)") (class "Default")
      (node (ref "VD13") (pin "1") (pinfunction "C_1") (pintype "passive"))
      (node (ref "VD15") (pin "1") (pinfunction "C_1") (pintype "passive"))
    )
    (net (code "44") (name "Net-(VD14-A)") (class "Default")
      (node (ref "R21") (pin "1") (pinfunction "1_1") (pintype "passive"))
      (node (ref "VD14") (pin "2") (pinfunction "A_2") (pintype "passive"))
    )
    (net (code "45") (name "Net-(VD16-A)") (class "Default")
      (node (ref "C12") (pin "2") (pinfunction "2_2") (pintype "passive"))
      (node (ref "T2") (pin "6") (pintype "passive"))
      (node (ref "VD16") (pin "2") (pinfunction "A_2") (pintype "passive"))
    )
    (net (code "46") (name "Net-(VD17-A)") (class "Default")
      (node (ref "R28") (pin "1") (pinfunction "1_1") (pintype "passive"))
      (node (ref "T2") (pin "2") (pintype "passive"))
      (node (ref "VD17") (pin "2") (pinfunction "A_2") (pintype "passive"))
      (node (ref "VD18") (pin "1") (pinfunction "C_1") (pintype "passive"))
    )
    (net (code "47") (name "Net-(VD17-C)") (class "Default")
      (node (ref "VD17") (pin "1") (pinfunction "C_1") (pintype "passive"))
      (node (ref "VD19") (pin "1") (pinfunction "C_1") (pintype "passive"))
    )
    (net (code "48") (name "Net-(VD18-A)") (class "Default")
      (node (ref "R39") (pin "1") (pinfunction "1_1") (pintype "passive"))
      (node (ref "VD18") (pin "2") (pinfunction "A_2") (pintype "passive"))
    )
    (net (code "49") (name "Net-(VD20-A)") (class "Default")
      (node (ref "C15") (pin "1") (pinfunction "1_1") (pintype "passive"))
      (node (ref "T3") (pin "10") (pintype "passive"))
      (node (ref "VD20") (pin "2") (pinfunction "A_2") (pintype "passive"))
    )
    (net (code "50") (name "Net-(VD20-C)") (class "Default")
      (node (ref "C15") (pin "2") (pinfunction "2_2") (pintype "passive"))
      (node (ref "VD20") (pin "1") (pinfunction "C_1") (pintype "passive"))
      (node (ref "VD23") (pin "3") (pinfunction "x_3") (pintype "passive"))
      (node (ref "VT4") (pin "3") (pinfunction "E_3") (pintype "passive"))
      (node (ref "VT5") (pin "3") (pinfunction "E_3") (pintype "passive"))
    )
    (net (code "51") (name "Net-(VD21-A)") (class "Default")
      (node (ref "R42") (pin "1") (pinfunction "1_1") (pintype "passive"))
      (node (ref "R43") (pin "2") (pinfunction "2_2") (pintype "passive"))
      (node (ref "VD21") (pin "2") (pinfunction "A_2") (pintype "passive"))
    )
    (net (code "52") (name "Net-(VD21-C)") (class "Default")
      (node (ref "VD21") (pin "1") (pinfunction "C_1") (pintype "passive"))
      (node (ref "VD22") (pin "1") (pinfunction "C_1") (pintype "passive"))
    )
    (net (code "53") (name "Net-(VD24-C)") (class "Default")
      (node (ref "VD24") (pin "1") (pinfunction "C_1") (pintype "passive"))
      (node (ref "VD25") (pin "1") (pinfunction "C_1") (pintype "passive"))
    )
    (net (code "54") (name "Net-(VD25-A)") (class "Default")
      (node (ref "R62") (pin "1") (pinfunction "1_1") (pintype "passive"))
      (node (ref "R63") (pin "2") (pinfunction "2_2") (pintype "passive"))
      (node (ref "VD25") (pin "2") (pinfunction "A_2") (pintype "passive"))
    )
    (net (code "55") (name "Net-(VD26-x)") (class "Default")
      (node (ref "C37") (pin "2") (pinfunction "2_2") (pintype "passive"))
      (node (ref "VD26") (pin "3") (pinfunction "x_3") (pintype "passive"))
      (node (ref "VD31") (pin "1") (pinfunction "C_1") (pintype "passive"))
      (node (ref "VT12") (pin "3") (pinfunction "E_3") (pintype "passive"))
      (node (ref "VT19") (pin "3") (pinfunction "D_3") (pintype "passive"))
      (node (ref "VT9") (pin "3") (pinfunction "E_3") (pintype "passive"))
    )
    (net (code "56") (name "Net-(VD27-x)") (class "Default")
      (node (ref "C34") (pin "1") (pinfunction "1_1") (pintype "passive"))
      (node (ref "VD27") (pin "3") (pinfunction "x_3") (pintype "passive"))
      (node (ref "VD29") (pin "1") (pinfunction "C_1") (pintype "passive"))
      (node (ref "VT11") (pin "3") (pinfunction "E_3") (pintype "passive"))
      (node (ref "VT8") (pin "3") (pinfunction "E_3") (pintype "passive"))
    )
    (net (code "57") (name "Net-(VD28-A)") (class "Default")
      (node (ref "R60") (pin "1") (pinfunction "1_1") (pintype "passive"))
      (node (ref "T5") (pin "1") (pintype "passive"))
      (node (ref "VD28") (pin "2") (pinfunction "A_2") (pintype "passive"))
      (node (ref "VD30") (pin "1") (pinfunction "C_1") (pintype "passive"))
    )
    (net (code "58") (name "Net-(VD28-C)") (class "Default")
      (node (ref "VD28") (pin "1") (pinfunction "C_1") (pintype "passive"))
      (node (ref "VD32") (pin "1") (pinfunction "C_1") (pintype "passive"))
    )
    (net (code "59") (name "Net-(VD29-A)") (class "Default")
      (node (ref "C34") (pin "2") (pinfunction "2_2") (pintype "passive"))
      (node (ref "T6") (pin "10") (pintype "passive"))
      (node (ref "VD29") (pin "2") (pinfunction "A_2") (pintype "passive"))
    )
    (net (code "60") (name "Net-(VD30-A)") (class "Default")
      (node (ref "R72") (pin "1") (pinfunction "1_1") (pintype "passive"))
      (node (ref "VD30") (pin "2") (pinfunction "A_2") (pintype "passive"))
    )
    (net (code "61") (name "Net-(VD31-A)") (class "Default")
      (node (ref "C37") (pin "1") (pinfunction "1_1") (pintype "passive"))
      (node (ref "T5") (pin "6") (pintype "passive"))
      (node (ref "VD31") (pin "2") (pinfunction "A_2") (pintype "passive"))
    )
    (net (code "62") (name "Net-(VD33-A)") (class "Default")
      (node (ref "R77") (pin "1") (pinfunction "1_1") (pintype "passive"))
      (node (ref "T5") (pin "3") (pintype "passive"))
      (node (ref "VD33") (pin "2") (pinfunction "A_2") (pintype "passive"))
      (node (ref "VD34") (pin "1") (pinfunction "C_1") (pintype "passive"))
    )
    (net (code "63") (name "Net-(VD33-C)") (class "Default")
      (node (ref "VD33") (pin "1") (pinfunction "C_1") (pintype "passive"))
      (node (ref "VD35") (pin "1") (pinfunction "C_1") (pintype "passive"))
    )
    (net (code "64") (name "Net-(VD34-A)") (class "Default")
      (node (ref "R79") (pin "1") (pinfunction "1_1") (pintype "passive"))
      (node (ref "VD34") (pin "2") (pinfunction "A_2") (pintype "passive"))
    )
    (net (code "65") (name "Net-(VT1-B)") (class "Default")
      (node (ref "R17") (pin "2") (pinfunction "2_2") (pintype "passive"))
      (node (ref "VT1") (pin "1") (pinfunction "B_1") (pintype "passive"))
      (node (ref "VT3") (pin "1") (pinfunction "B_1") (pintype "passive"))
    )
    (net (code "66") (name "Net-(VT2-B)") (class "Default")
      (node (ref "R42") (pin "2") (pinfunction "2_2") (pintype "passive"))
      (node (ref "VT2") (pin "1") (pinfunction "B_1") (pintype "passive"))
      (node (ref "VT6") (pin "1") (pinfunction "B_1") (pintype "passive"))
    )
    (net (code "67") (name "Net-(VT2-C)") (class "Default")
      (node (ref "C13") (pin "2") (pinfunction "2_2") (pintype "passive"))
      (node (ref "R22") (pin "2") (pinfunction "2_2") (pintype "passive"))
      (node (ref "VT2") (pin "2") (pinfunction "C_2") (pintype "passive"))
    )
    (net (code "68") (name "Net-(VT4-B)") (class "Default")
      (node (ref "R44") (pin "2") (pinfunction "2_2") (pintype "passive"))
      (node (ref "VT4") (pin "1") (pinfunction "B_1") (pintype "passive"))
      (node (ref "VT5") (pin "1") (pinfunction "B_1") (pintype "passive"))
    )
    (net (code "69") (name "Net-(VT10-B)") (class "Default")
      (node (ref "R62") (pin "2") (pinfunction "2_2") (pintype "passive"))
      (node (ref "VT10") (pin "1") (pinfunction "B_1") (pintype "passive"))
      (node (ref "VT7") (pin "1") (pinfunction "B_1") (pintype "passive"))
    )
    (net (code "70") (name "Net-(VT10-C)") (class "Default")
      (node (ref "C38") (pin "2") (pinfunction "2_2") (pintype "passive"))
      (node (ref "R76") (pin "2") (pinfunction "2_2") (pintype "passive"))
      (node (ref "VT10") (pin "2") (pinfunction "C_2") (pintype "passive"))
    )
    (net (code "71") (name "Net-(VT11-B)") (class "Default")
      (node (ref "R65") (pin "2") (pinfunction "2_2") (pintype "passive"))
      (node (ref "VT11") (pin "1") (pinfunction "B_1") (pintype "passive"))
      (node (ref "VT8") (pin "1") (pinfunction "B_1") (pintype "passive"))
    )
    (net (code "72") (name "Net-(VT12-B)") (class "Default")
      (node (ref "R74") (pin "2") (pinfunction "2_2") (pintype "passive"))
      (node (ref "VT12") (pin "1") (pinfunction "B_1") (pintype "passive"))
      (node (ref "VT9") (pin "1") (pinfunction "B_1") (pintype "passive"))
    )
    (net (code "73") (name "unconnected-(DD1-OSC_OUT-Pad4)") (class "Default")
      (node (ref "DD1") (pin "4") (pinfunction "OSC_OUT_4") (pintype "passive"))
    )
  )
)
